# Fuente_Alimentacion_sin_regulador.net
KiCad netlist of a schematic drawn in EAGLE
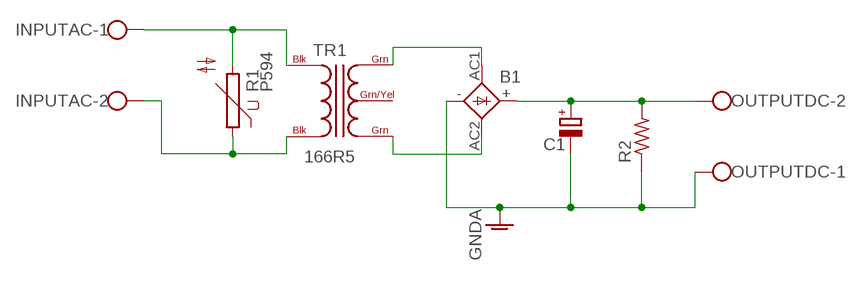
[diagram p0: schematic, sheet 1]

(export (version "E")
  (design (tool "Eeschema 10.0.6"))
  (components
    (comp (ref "B1")
      (value "GBPC1")
      (footprint "eagle-import:GBPC1")
      (libsource (lib "eagle-import") (part "GBPC1"))
    )
    (comp (ref "C1")
      (value "CPOL-EU153CLV-1012")
      (footprint "eagle-import:153CLV-1012")
      (libsource (lib "eagle-import") (part "CPOL-EU153CLV-1012"))
    )
    (comp (ref "INPUTAC")
      (value "W237-102")
      (footprint "eagle-import:W237-102")
      (fields (field (name "MPN") "237-102"))
      (libsource (lib "eagle-import") (part "W237-102"))
    )
    (comp (ref "OUTPUTDC")
      (value "W237-102")
      (footprint "eagle-import:W237-102")
      (fields (field (name "MPN") "237-102"))
      (libsource (lib "eagle-import") (part "W237-102"))
    )
    (comp (ref "R1")
      (value "P594")
      (footprint "eagle-import:P594")
      (libsource (lib "eagle-import") (part "P594"))
    )
    (comp (ref "R2")
      (value "R-US_0207/10")
      (footprint "eagle-import:0207_10")
      (libsource (lib "eagle-import") (part "R-US_0207/10"))
    )
    (comp (ref "TR1")
      (value "166R5")
      (footprint "eagle-import:C12H")
      (libsource (lib "eagle-import") (part "166R5"))
    )
  )
  (nets
    (net (code "1") (name "GNDA") (class "Default")
      (node (ref "B1") (pin "-") (pinfunction "-_-") (pintype "passive"))
      (node (ref "C1") (pin "-") (pinfunction "-_-") (pintype "passive"))
      (node (ref "OUTPUTDC") (pin "1") (pinfunction "KL_1") (pintype "passive"))
      (node (ref "R2") (pin "1") (pinfunction "1_1") (pintype "passive"))
    )
    (net (code "2") (name "Net-(B1-PadAC1)") (class "Default")
      (node (ref "B1") (pin "AC1") (pinfunction "AC1_AC1") (pintype "passive"))
      (node (ref "TR1") (pin "GRN@1") (pinfunction "GRN_GRN@1") (pintype "passive"))
    )
    (net (code "3") (name "Net-(B1-PadAC2)") (class "Default")
      (node (ref "B1") (pin "AC2") (pinfunction "AC2_AC2") (pintype "passive"))
      (node (ref "TR1") (pin "GRN@2") (pinfunction "GRN_GRN@2") (pintype "passive"))
    )
    (net (code "4") (name "Net-(INPUTACA-KL)") (class "Default")
      (node (ref "INPUTAC") (pin "1") (pinfunction "KL_1") (pintype "passive"))
      (node (ref "R1") (pin "2") (pinfunction "2_2") (pintype "passive"))
      (node (ref "TR1") (pin "BLK@1") (pinfunction "BLK_BLK@1") (pintype "passive"))
    )
    (net (code "5") (name "Net-(INPUTACB-KL)") (class "Default")
      (node (ref "INPUTAC") (pin "2") (pinfunction "KL_2") (pintype "passive"))
      (node (ref "R1") (pin "1") (pinfunction "1_1") (pintype "passive"))
      (node (ref "TR1") (pin "BLK@2") (pinfunction "BLK_BLK@2") (pintype "passive"))
    )
    (net (code "6") (name "Net-(OUTPUTDCB-KL)") (class "Default")
      (node (ref "B1") (pin "+") (pinfunction "+_+") (pintype "passive"))
      (node (ref "C1") (pin "+") (pinfunction "+_+") (pintype "passive"))
      (node (ref "OUTPUTDC") (pin "2") (pinfunction "KL_2") (pintype "passive"))
      (node (ref "R2") (pin "2") (pinfunction "2_2") (pintype "passive"))
    )
    (net (code "7") (name "unconnected-(TR1-PadGRN{slash}YEL)") (class "Default")
      (node (ref "TR1") (pin "GRN/YEL") (pinfunction "GRN/YEL_GRN/YEL") (pintype "passive"))
    )
  )
)
